# MCISO-S06-V00-PSU3V3.net
KiCad netlist of a schematic drawn in Altium Designer
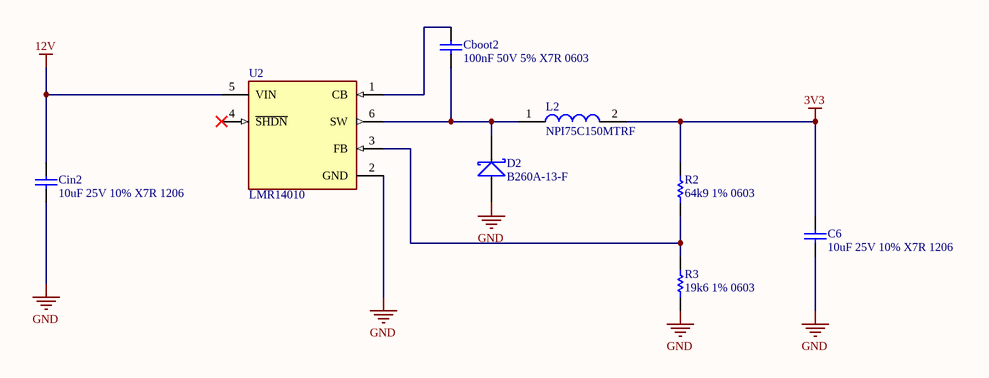
[diagram p0: MCISO-S06-V00-PSU3V3.SchDoc]

(export (version "E")
  (design (tool "Eeschema 10.0.6"))
  (components
    (comp (ref "C6")
      (value "10uF 25V 10% X7R 1206")
      (footprint "Cap_Ceramic_1206")
      (description "Capacitor, Ceramic, SMD, 10uF, 25V, 10%, X7R, 1206")
      (libsource (lib "QUTMS-MCISOLibrary") (part "10uF 25V 10% X7R 1206"))
    )
    (comp (ref "Cboot2")
      (value "100nF 50V 5% X7R 0603")
      (footprint "Cap_Ceramic_0603")
      (description "Capacitor, Ceramic, SMD, 100nF, 50V, 5%, X7R, 0603")
      (libsource (lib "StandardCapacitors") (part "100nF 50V 5% X7R 0603"))
    )
    (comp (ref "Cin2")
      (value "10uF 25V 10% X7R 1206")
      (footprint "Cap_Ceramic_1206")
      (description "Capacitor, Ceramic, SMD, 10uF, 25V, 10%, X7R, 1206")
      (libsource (lib "StandardCapacitors") (part "10uF 25V 10% X7R 1206"))
    )
    (comp (ref "D2")
      (value "B260A-13-F")
      (footprint "SMA")
      (description "Diode, Schottky Barrier Rectifier, 60 V, 2 A, B260A-13-F")
      (libsource (lib "QUTMS_DiodeLibrary") (part "B260A-13-F"))
    )
    (comp (ref "L2")
      (value "NPI75C150MTRF")
      (footprint "NPI75C150MTRF")
      (description "Ind Power Unshielded Wirewound 15uH 20% 1KHz 1.8A T/R")
      (libsource (lib "QUTMS-MCISOLibrary") (part "NPI75C150MTRF"))
    )
    (comp (ref "R2")
      (value "64k9 1% 0603")
      (footprint "Res_ThinFilm_0603")
      (description "Resistor, SMD, 64k9, 0.1W, 5%, 0603")
      (libsource (lib "QUTMS-MCISOLibrary") (part "64k9 1% 0603"))
    )
    (comp (ref "R3")
      (value "19k6 1% 0603")
      (footprint "Res_ThinFilm_0603")
      (description "Resistor, SMD, 19k6, 0.1W, 5%, 0603")
      (libsource (lib "QUTMS-MCISOLibrary") (part "19k6 1% 0603"))
    )
    (comp (ref "U2")
      (value "LMR14010")
      (footprint "LMR14010")
      (libsource (lib "QUTMS_PowerSupplyLibrary") (part "LMR14010"))
    )
  )
  (nets
    (net (code "1") (name "3V3") (class "Default")
      (node (ref "C6") (pin "2") (pinfunction "2_2") (pintype "passive"))
      (node (ref "L2") (pin "2") (pinfunction "2_2") (pintype "passive"))
      (node (ref "R2") (pin "2") (pinfunction "2_2") (pintype "passive"))
    )
    (net (code "2") (name "12V") (class "Default")
      (node (ref "Cin2") (pin "2") (pinfunction "2_2") (pintype "passive"))
      (node (ref "U2") (pin "5") (pinfunction "VIN_5") (pintype "power_in"))
    )
    (net (code "3") (name "GND") (class "Default")
      (node (ref "C6") (pin "1") (pinfunction "1_1") (pintype "passive"))
      (node (ref "Cin2") (pin "1") (pinfunction "1_1") (pintype "passive"))
      (node (ref "D2") (pin "A") (pinfunction "A_A") (pintype "passive"))
      (node (ref "R3") (pin "1") (pinfunction "1_1") (pintype "passive"))
      (node (ref "U2") (pin "2") (pinfunction "GND_2") (pintype "power_in"))
    )
    (net (code "4") (name "Net-(U2-CB)") (class "Default")
      (node (ref "Cboot2") (pin "2") (pinfunction "2_2") (pintype "passive"))
      (node (ref "U2") (pin "1") (pinfunction "CB_1") (pintype "input"))
    )
    (net (code "5") (name "Net-(U2-FB)") (class "Default")
      (node (ref "R2") (pin "1") (pinfunction "1_1") (pintype "passive"))
      (node (ref "R3") (pin "2") (pinfunction "2_2") (pintype "passive"))
      (node (ref "U2") (pin "3") (pinfunction "FB_3") (pintype "input"))
    )
    (net (code "6") (name "Net-(U2-SW)") (class "Default")
      (node (ref "Cboot2") (pin "1") (pinfunction "1_1") (pintype "passive"))
      (node (ref "D2") (pin "K") (pinfunction "K_K") (pintype "passive"))
      (node (ref "L2") (pin "1") (pinfunction "1_1") (pintype "passive"))
      (node (ref "U2") (pin "6") (pinfunction "SW_6") (pintype "output"))
    )
    (net (code "7") (name "unconnected-(U2-~{SHDN}-Pad4)") (class "Default")
      (node (ref "U2") (pin "4") (pinfunction "~{SHDN}_4") (pintype "input+no_connect"))
    )
  )
)
